# TDII_CPU_R00.net
KiCad netlist of a schematic drawn in Altium Designer
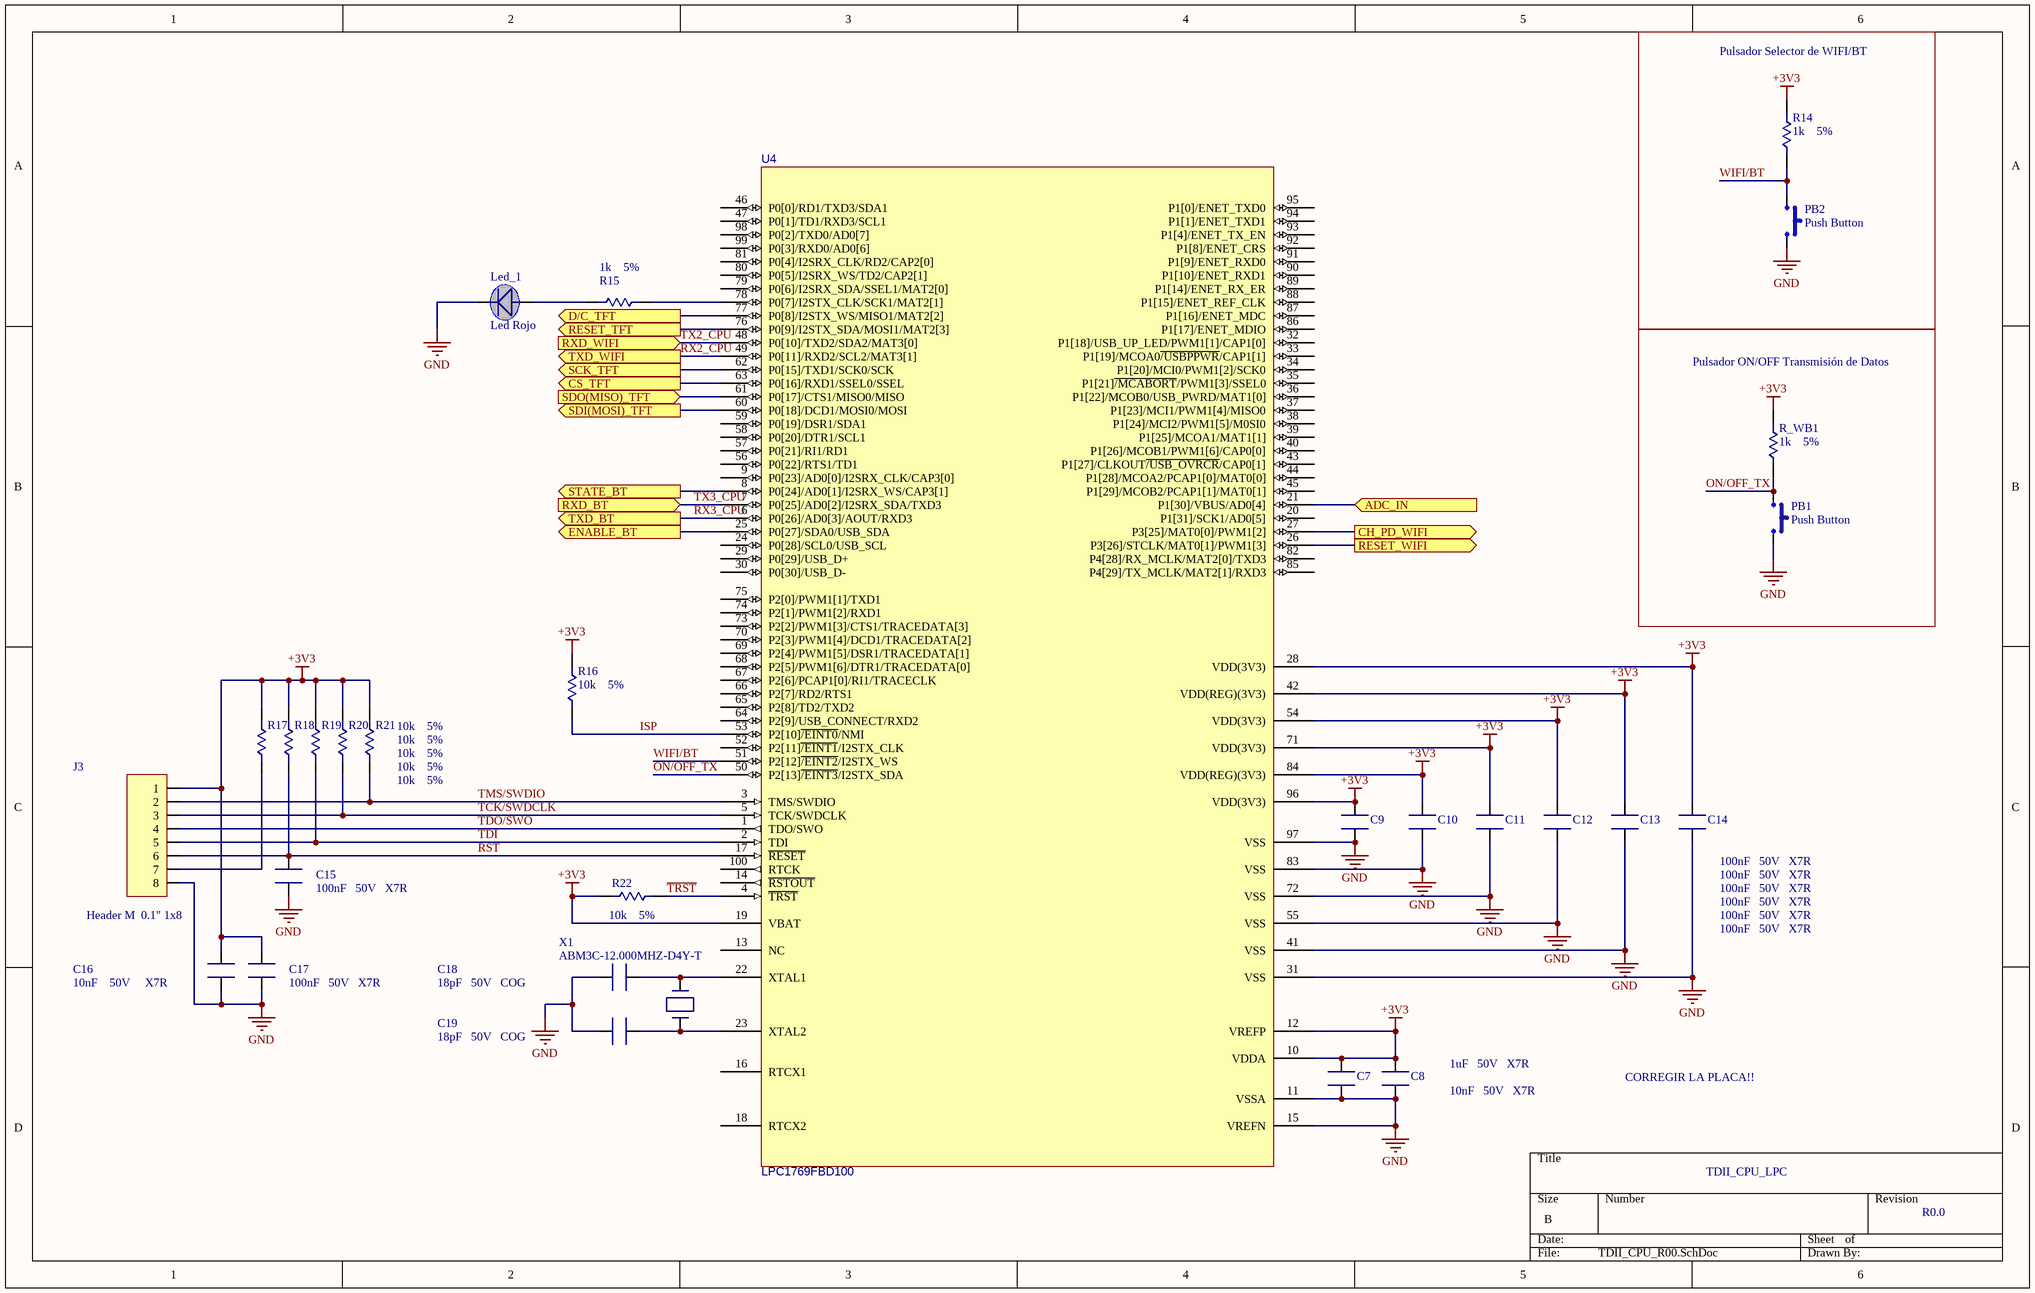
[diagram p0: TDII_CPU_R00.SchDoc]

(export (version "E")
  (design (tool "Eeschema 10.0.6"))
  (components
    (comp (ref "C7")
      (value "10nF   50V   X7R")
      (footprint "C_0805")
      (libsource (lib "TDII_SCH_LIB_R00") (part "CAP"))
    )
    (comp (ref "C8")
      (value "1uF   50V   X7R")
      (footprint "C_0805")
      (libsource (lib "TDII_SCH_LIB_R00") (part "CAP"))
    )
    (comp (ref "C9")
      (value "100nF   50V   X7R")
      (footprint "C_0805")
      (libsource (lib "TDII_SCH_LIB_R00") (part "CAP"))
    )
    (comp (ref "C10")
      (value "100nF   50V   X7R")
      (footprint "C_0805")
      (libsource (lib "TDII_SCH_LIB_R00") (part "CAP"))
    )
    (comp (ref "C11")
      (value "100nF   50V   X7R")
      (footprint "C_0805")
      (libsource (lib "TDII_SCH_LIB_R00") (part "CAP"))
    )
    (comp (ref "C12")
      (value "100nF   50V   X7R")
      (footprint "C_0805")
      (libsource (lib "TDII_SCH_LIB_R00") (part "CAP"))
    )
    (comp (ref "C13")
      (value "100nF   50V   X7R")
      (footprint "C_0805")
      (libsource (lib "TDII_SCH_LIB_R00") (part "CAP"))
    )
    (comp (ref "C14")
      (value "100nF   50V   X7R")
      (footprint "C_0805")
      (libsource (lib "TDII_SCH_LIB_R00") (part "CAP"))
    )
    (comp (ref "C15") (value "100nF   50V   X7R") (footprint "C_0805") (libsource (lib "") (part "CAP_1")))
    (comp (ref "C16") (value "10nF    50V     X7R") (footprint "C_0805") (libsource (lib "") (part "CAP_1")))
    (comp (ref "C17") (value "100nF   50V   X7R") (footprint "C_0805") (libsource (lib "") (part "CAP_1")))
    (comp (ref "C18")
      (value "18pF   50V   COG")
      (footprint "C_0805")
      (libsource (lib "TDII_SCH_LIB_R00") (part "CAP"))
    )
    (comp (ref "C19")
      (value "18pF   50V   COG")
      (footprint "C_0805")
      (libsource (lib "TDII_SCH_LIB_R00") (part "CAP"))
    )
    (comp (ref "J3")
      (value "Header M  0.1\" 1x8")
      (footprint "Header_THT")
      (libsource (lib "TDII_SCH_LIB_R00") (part "Header"))
    )
    (comp (ref "Led_1")
      (value "Led Rojo")
      (footprint "LED_0805")
      (libsource (lib "TDII_SCH_LIB_R00") (part "LED"))
    )
    (comp (ref "PB1")
      (value "Push Button")
      (footprint "HEADER_1x2")
      (libsource (lib "IFS_Altium") (part "Push Button"))
    )
    (comp (ref "PB2")
      (value "Push Button")
      (footprint "HEADER_1x2")
      (libsource (lib "IFS_Altium") (part "Push Button"))
    )
    (comp (ref "R14")
      (value "1k    5%")
      (footprint "R_0805")
      (libsource (lib "TDII_SCH_LIB_R00") (part "RES"))
    )
    (comp (ref "R15")
      (value "1k    5%")
      (footprint "R_0805")
      (libsource (lib "TDII_SCH_LIB_R00") (part "RES"))
    )
    (comp (ref "R16")
      (value "10k    5%")
      (footprint "R_0805")
      (libsource (lib "TDII_SCH_LIB_R00") (part "RES"))
    )
    (comp (ref "R17")
      (value "10k    5%")
      (footprint "R_0805")
      (libsource (lib "TDII_SCH_LIB_R00") (part "RES"))
    )
    (comp (ref "R18")
      (value "10k    5%")
      (footprint "R_0805")
      (libsource (lib "TDII_SCH_LIB_R00") (part "RES"))
    )
    (comp (ref "R19")
      (value "10k    5%")
      (footprint "R_0805")
      (libsource (lib "TDII_SCH_LIB_R00") (part "RES"))
    )
    (comp (ref "R20")
      (value "10k    5%")
      (footprint "R_0805")
      (libsource (lib "TDII_SCH_LIB_R00") (part "RES"))
    )
    (comp (ref "R21")
      (value "10k    5%")
      (footprint "R_0805")
      (libsource (lib "TDII_SCH_LIB_R00") (part "RES"))
    )
    (comp (ref "R22")
      (value "10k    5%")
      (footprint "R_0805")
      (libsource (lib "TDII_SCH_LIB_R00") (part "RES"))
    )
    (comp (ref "R_WB1")
      (value "1k    5%")
      (footprint "R_0805")
      (libsource (lib "TDII_SCH_LIB_R00") (part "RES"))
    )
    (comp (ref "U4")
      (value "LPC1769FBD100")
      (footprint "LQFP100")
      (description "CPU Cortex M3")
      (fields (field (name "DIGI-KEY PART NUMBER") "568-4966-ND"))
      (libsource (lib "TdiiCpu") (part "LPC1768FBD100"))
    )
    (comp (ref "X1")
      (value "ABM3C-12.000MHZ-D4Y-T")
      (footprint "ABM3C")
      (fields (field (name "DIGI-KEY PART NUMBER") "535-11281-1-ND"))
      (libsource (lib "TDII_SCH_LIB_R00") (part "ABM3_CRISTAL"))
    )
  )
  (nets
    (net (code "1") (name "+3V3") (class "Default")
      (node (ref "C10") (pin "1") (pinfunction "1_1") (pintype "passive"))
      (node (ref "C11") (pin "1") (pinfunction "1_1") (pintype "passive"))
      (node (ref "C12") (pin "1") (pinfunction "1_1") (pintype "passive"))
      (node (ref "C13") (pin "1") (pinfunction "1_1") (pintype "passive"))
      (node (ref "C14") (pin "1") (pinfunction "1_1") (pintype "passive"))
      (node (ref "C16") (pin "1") (pinfunction "1_1") (pintype "passive"))
      (node (ref "C17") (pin "1") (pinfunction "1_1") (pintype "passive"))
      (node (ref "C7") (pin "1") (pinfunction "1_1") (pintype "passive"))
      (node (ref "C8") (pin "1") (pinfunction "1_1") (pintype "passive"))
      (node (ref "C9") (pin "1") (pinfunction "1_1") (pintype "passive"))
      (node (ref "J3") (pin "1") (pinfunction "1_1") (pintype "passive"))
      (node (ref "R14") (pin "2") (pinfunction "2_2") (pintype "passive"))
      (node (ref "R16") (pin "2") (pinfunction "2_2") (pintype "passive"))
      (node (ref "R17") (pin "2") (pinfunction "2_2") (pintype "passive"))
      (node (ref "R18") (pin "2") (pinfunction "2_2") (pintype "passive"))
      (node (ref "R19") (pin "2") (pinfunction "2_2") (pintype "passive"))
      (node (ref "R20") (pin "2") (pinfunction "2_2") (pintype "passive"))
      (node (ref "R21") (pin "2") (pinfunction "2_2") (pintype "passive"))
      (node (ref "R22") (pin "1") (pinfunction "1_1") (pintype "passive"))
      (node (ref "R_WB1") (pin "2") (pinfunction "2_2") (pintype "passive"))
      (node (ref "U4") (pin "10") (pinfunction "VDDA_10") (pintype "power_in"))
      (node (ref "U4") (pin "12") (pinfunction "VREFP_12") (pintype "power_in"))
      (node (ref "U4") (pin "19") (pinfunction "VBAT_19") (pintype "power_in"))
      (node (ref "U4") (pin "28") (pinfunction "VDD(3V3)_28") (pintype "power_in"))
      (node (ref "U4") (pin "42") (pinfunction "VDD(REG)(3V3)_42") (pintype "power_in"))
      (node (ref "U4") (pin "54") (pinfunction "VDD(3V3)_54") (pintype "power_in"))
      (node (ref "U4") (pin "71") (pinfunction "VDD(3V3)_71") (pintype "power_in"))
      (node (ref "U4") (pin "84") (pinfunction "VDD(REG)(3V3)_84") (pintype "power_in"))
      (node (ref "U4") (pin "96") (pinfunction "VDD(3V3)_96") (pintype "power_in"))
    )
    (net (code "2") (name "/ADC_IN") (class "Default")
      (node (ref "U4") (pin "21") (pinfunction "P1[30]/VBUS/AD0[4]_21") (pintype "bidirectional"))
    )
    (net (code "3") (name "/CH_PD_WIFI") (class "Default")
      (node (ref "U4") (pin "27") (pinfunction "P3[25]/MAT0[0]/PWM1[2]_27") (pintype "bidirectional"))
    )
    (net (code "4") (name "/CS_TFT") (class "Default")
      (node (ref "U4") (pin "63") (pinfunction "P0[16]/RXD1/SSEL0/SSEL_63") (pintype "bidirectional"))
    )
    (net (code "5") (name "/D{slash}C_TFT") (class "Default")
      (node (ref "U4") (pin "77") (pinfunction "P0[8]/I2STX_WS/MISO1/MAT2[2]_77") (pintype "bidirectional"))
    )
    (net (code "6") (name "/ENABLE_BT") (class "Default")
      (node (ref "U4") (pin "25") (pinfunction "P0[27]/SDA0/USB_SDA_25") (pintype "bidirectional"))
    )
    (net (code "7") (name "/ISP") (class "Default")
      (node (ref "R16") (pin "1") (pinfunction "1_1") (pintype "passive"))
      (node (ref "U4") (pin "53") (pinfunction "P2[10]~{/EINT0}/NMI_53") (pintype "bidirectional"))
    )
    (net (code "8") (name "/ON{slash}OFF_TX") (class "Default")
      (node (ref "PB1") (pin "1") (pinfunction "1_1") (pintype "passive"))
      (node (ref "R_WB1") (pin "1") (pinfunction "1_1") (pintype "passive"))
      (node (ref "U4") (pin "50") (pinfunction "P2[13]~{/EINT3}/I2STX_SDA_50") (pintype "bidirectional"))
    )
    (net (code "9") (name "/RESET_TFT") (class "Default")
      (node (ref "U4") (pin "76") (pinfunction "P0[9]/I2STX_SDA/MOSI1/MAT2[3]_76") (pintype "bidirectional"))
    )
    (net (code "10") (name "/RESET_WIFI") (class "Default")
      (node (ref "U4") (pin "26") (pinfunction "P3[26]/STCLK/MAT0[1]/PWM1[3]_26") (pintype "bidirectional"))
    )
    (net (code "11") (name "/RST") (class "Default")
      (node (ref "C15") (pin "1") (pinfunction "1_1") (pintype "passive"))
      (node (ref "J3") (pin "6") (pinfunction "6_6") (pintype "passive"))
      (node (ref "R18") (pin "1") (pinfunction "1_1") (pintype "passive"))
      (node (ref "U4") (pin "17") (pinfunction "~{RESET}_17") (pintype "input"))
    )
    (net (code "12") (name "/RX2_CPU") (class "Default")
      (node (ref "U4") (pin "49") (pinfunction "P0[11]/RXD2/SCL2/MAT3[1]_49") (pintype "bidirectional"))
    )
    (net (code "13") (name "/RX3_CPU") (class "Default")
      (node (ref "U4") (pin "6") (pinfunction "P0[26]/AD0[3]/AOUT/RXD3_6") (pintype "bidirectional"))
    )
    (net (code "14") (name "/SCK_TFT") (class "Default")
      (node (ref "U4") (pin "62") (pinfunction "P0[15]/TXD1/SCK0/SCK_62") (pintype "bidirectional"))
    )
    (net (code "15") (name "/SDI(MOSI)_TFT") (class "Default")
      (node (ref "U4") (pin "60") (pinfunction "P0[18]/DCD1/MOSI0/MOSI_60") (pintype "bidirectional"))
    )
    (net (code "16") (name "/SDO(MISO)_TFT") (class "Default")
      (node (ref "U4") (pin "61") (pinfunction "P0[17]/CTS1/MISO0/MISO_61") (pintype "bidirectional"))
    )
    (net (code "17") (name "/STATE_BT") (class "Default")
      (node (ref "U4") (pin "8") (pinfunction "P0[24]/AD0[1]/I2SRX_WS/CAP3[1]_8") (pintype "bidirectional"))
    )
    (net (code "18") (name "/TCK{slash}SWDCLK") (class "Default")
      (node (ref "J3") (pin "3") (pinfunction "3_3") (pintype "passive"))
      (node (ref "R20") (pin "1") (pinfunction "1_1") (pintype "passive"))
      (node (ref "U4") (pin "5") (pinfunction "TCK/SWDCLK_5") (pintype "input"))
    )
    (net (code "19") (name "/TDI") (class "Default")
      (node (ref "J3") (pin "5") (pinfunction "5_5") (pintype "passive"))
      (node (ref "R19") (pin "1") (pinfunction "1_1") (pintype "passive"))
      (node (ref "U4") (pin "2") (pinfunction "TDI_2") (pintype "input"))
    )
    (net (code "20") (name "/TDO{slash}SWO") (class "Default")
      (node (ref "J3") (pin "4") (pinfunction "4_4") (pintype "passive"))
      (node (ref "U4") (pin "1") (pinfunction "TDO/SWO_1") (pintype "output"))
    )
    (net (code "21") (name "/TMS{slash}SWDIO") (class "Default")
      (node (ref "J3") (pin "2") (pinfunction "2_2") (pintype "passive"))
      (node (ref "R21") (pin "1") (pinfunction "1_1") (pintype "passive"))
      (node (ref "U4") (pin "3") (pinfunction "TMS/SWDIO_3") (pintype "input"))
    )
    (net (code "22") (name "/TX2_CPU") (class "Default")
      (node (ref "U4") (pin "48") (pinfunction "P0[10]/TXD2/SDA2/MAT3[0]_48") (pintype "bidirectional"))
    )
    (net (code "23") (name "/TX3_CPU") (class "Default")
      (node (ref "U4") (pin "7") (pinfunction "P0[25]/AD0[2]/I2SRX_SDA/TXD3_7") (pintype "bidirectional"))
    )
    (net (code "24") (name "/WIFI{slash}BT") (class "Default")
      (node (ref "PB2") (pin "1") (pinfunction "1_1") (pintype "passive"))
      (node (ref "R14") (pin "1") (pinfunction "1_1") (pintype "passive"))
      (node (ref "U4") (pin "51") (pinfunction "P2[12]~{/EINT2}/I2STX_WS_51") (pintype "bidirectional"))
    )
    (net (code "25") (name "/~{TRST}") (class "Default")
      (node (ref "R22") (pin "2") (pinfunction "2_2") (pintype "passive"))
      (node (ref "U4") (pin "4") (pinfunction "~{TRST}_4") (pintype "input"))
    )
    (net (code "26") (name "GND") (class "Default")
      (node (ref "C10") (pin "2") (pinfunction "2_2") (pintype "passive"))
      (node (ref "C11") (pin "2") (pinfunction "2_2") (pintype "passive"))
      (node (ref "C12") (pin "2") (pinfunction "2_2") (pintype "passive"))
      (node (ref "C13") (pin "2") (pinfunction "2_2") (pintype "passive"))
      (node (ref "C14") (pin "2") (pinfunction "2_2") (pintype "passive"))
      (node (ref "C15") (pin "2") (pinfunction "2_2") (pintype "passive"))
      (node (ref "C16") (pin "2") (pinfunction "2_2") (pintype "passive"))
      (node (ref "C17") (pin "2") (pinfunction "2_2") (pintype "passive"))
      (node (ref "C18") (pin "1") (pinfunction "1_1") (pintype "passive"))
      (node (ref "C19") (pin "1") (pinfunction "1_1") (pintype "passive"))
      (node (ref "C7") (pin "2") (pinfunction "2_2") (pintype "passive"))
      (node (ref "C8") (pin "2") (pinfunction "2_2") (pintype "passive"))
      (node (ref "C9") (pin "2") (pinfunction "2_2") (pintype "passive"))
      (node (ref "J3") (pin "8") (pinfunction "8_8") (pintype "passive"))
      (node (ref "Led_1") (pin "2") (pinfunction "2_2") (pintype "passive"))
      (node (ref "PB1") (pin "2") (pinfunction "2_2") (pintype "passive"))
      (node (ref "PB2") (pin "2") (pinfunction "2_2") (pintype "passive"))
      (node (ref "U4") (pin "11") (pinfunction "VSSA_11") (pintype "power_in"))
      (node (ref "U4") (pin "15") (pinfunction "VREFN_15") (pintype "power_in"))
      (node (ref "U4") (pin "31") (pinfunction "VSS_31") (pintype "power_in"))
      (node (ref "U4") (pin "41") (pinfunction "VSS_41") (pintype "power_in"))
      (node (ref "U4") (pin "55") (pinfunction "VSS_55") (pintype "power_in"))
      (node (ref "U4") (pin "72") (pinfunction "VSS_72") (pintype "power_in"))
      (node (ref "U4") (pin "83") (pinfunction "VSS_83") (pintype "power_in"))
      (node (ref "U4") (pin "97") (pinfunction "VSS_97") (pintype "power_in"))
    )
    (net (code "27") (name "Net-(J3-Pad7)") (class "Default")
      (node (ref "J3") (pin "7") (pinfunction "7_7") (pintype "passive"))
      (node (ref "R17") (pin "1") (pinfunction "1_1") (pintype "passive"))
    )
    (net (code "28") (name "Net-(Led_1-Pad1)") (class "Default")
      (node (ref "Led_1") (pin "1") (pinfunction "1_1") (pintype "passive"))
      (node (ref "R15") (pin "1") (pinfunction "1_1") (pintype "passive"))
    )
    (net (code "29") (name "Net-(U4-P0[7]{slash}I2STX_CLK{slash}SCK1{slash}MAT2[1])") (class "Default")
      (node (ref "R15") (pin "2") (pinfunction "2_2") (pintype "passive"))
      (node (ref "U4") (pin "78") (pinfunction "P0[7]/I2STX_CLK/SCK1/MAT2[1]_78") (pintype "bidirectional"))
    )
    (net (code "30") (name "Net-(U4-XTAL1)") (class "Default")
      (node (ref "C18") (pin "2") (pinfunction "2_2") (pintype "passive"))
      (node (ref "U4") (pin "22") (pinfunction "XTAL1_22") (pintype "passive"))
      (node (ref "X1") (pin "1") (pinfunction "1_1") (pintype "passive"))
    )
    (net (code "31") (name "Net-(U4-XTAL2)") (class "Default")
      (node (ref "C19") (pin "2") (pinfunction "2_2") (pintype "passive"))
      (node (ref "U4") (pin "23") (pinfunction "XTAL2_23") (pintype "passive"))
      (node (ref "X1") (pin "3") (pinfunction "3_3") (pintype "passive"))
    )
    (net (code "32") (name "unconnected-(U4-NC-Pad13)") (class "Default")
      (node (ref "U4") (pin "13") (pinfunction "NC_13") (pintype "passive"))
    )
    (net (code "33") (name "unconnected-(U4-P0[0]{slash}RD1{slash}TXD3{slash}SDA1-Pad46)") (class "Default")
      (node (ref "U4") (pin "46") (pinfunction "P0[0]/RD1/TXD3/SDA1_46") (pintype "bidirectional"))
    )
    (net (code "34") (name "unconnected-(U4-P0[1]{slash}TD1{slash}RXD3{slash}SCL1-Pad47)") (class "Default")
      (node (ref "U4") (pin "47") (pinfunction "P0[1]/TD1/RXD3/SCL1_47") (pintype "bidirectional"))
    )
    (net (code "35") (name "unconnected-(U4-P0[2]{slash}TXD0{slash}AD0[7]-Pad98)") (class "Default")
      (node (ref "U4") (pin "98") (pinfunction "P0[2]/TXD0/AD0[7]_98") (pintype "bidirectional"))
    )
    (net (code "36") (name "unconnected-(U4-P0[3]{slash}RXD0{slash}AD0[6]-Pad99)") (class "Default")
      (node (ref "U4") (pin "99") (pinfunction "P0[3]/RXD0/AD0[6]_99") (pintype "bidirectional"))
    )
    (net (code "37") (name "unconnected-(U4-P0[4]{slash}I2SRX_CLK{slash}RD2{slash}CAP2[0]-Pad81)") (class "Default")
      (node (ref "U4") (pin "81") (pinfunction "P0[4]/I2SRX_CLK/RD2/CAP2[0]_81") (pintype "bidirectional"))
    )
    (net (code "38") (name "unconnected-(U4-P0[5]{slash}I2SRX_WS{slash}TD2{slash}CAP2[1]-Pad80)") (class "Default")
      (node (ref "U4") (pin "80") (pinfunction "P0[5]/I2SRX_WS/TD2/CAP2[1]_80") (pintype "bidirectional"))
    )
    (net (code "39") (name "unconnected-(U4-P0[6]{slash}I2SRX_SDA{slash}SSEL1{slash}MAT2[0]-Pad79)") (class "Default")
      (node (ref "U4") (pin "79") (pinfunction "P0[6]/I2SRX_SDA/SSEL1/MAT2[0]_79") (pintype "bidirectional"))
    )
    (net (code "40") (name "unconnected-(U4-P0[19]{slash}DSR1{slash}SDA1-Pad59)") (class "Default")
      (node (ref "U4") (pin "59") (pinfunction "P0[19]/DSR1/SDA1_59") (pintype "bidirectional"))
    )
    (net (code "41") (name "unconnected-(U4-P0[20]{slash}DTR1{slash}SCL1-Pad58)") (class "Default")
      (node (ref "U4") (pin "58") (pinfunction "P0[20]/DTR1/SCL1_58") (pintype "bidirectional"))
    )
    (net (code "42") (name "unconnected-(U4-P0[21]{slash}RI1{slash}RD1-Pad57)") (class "Default")
      (node (ref "U4") (pin "57") (pinfunction "P0[21]/RI1/RD1_57") (pintype "bidirectional"))
    )
    (net (code "43") (name "unconnected-(U4-P0[22]{slash}RTS1{slash}TD1-Pad56)") (class "Default")
      (node (ref "U4") (pin "56") (pinfunction "P0[22]/RTS1/TD1_56") (pintype "bidirectional"))
    )
    (net (code "44") (name "unconnected-(U4-P0[23]{slash}AD0[0]{slash}I2SRX_CLK{slash}CAP3[0]-Pad9)") (class "Default")
      (node (ref "U4") (pin "9") (pinfunction "P0[23]/AD0[0]/I2SRX_CLK/CAP3[0]_9") (pintype "bidirectional"))
    )
    (net (code "45") (name "unconnected-(U4-P0[28]{slash}SCL0{slash}USB_SCL-Pad24)") (class "Default")
      (node (ref "U4") (pin "24") (pinfunction "P0[28]/SCL0/USB_SCL_24") (pintype "bidirectional"))
    )
    (net (code "46") (name "unconnected-(U4-P0[29]{slash}USB_D+-Pad29)") (class "Default")
      (node (ref "U4") (pin "29") (pinfunction "P0[29]/USB_D+_29") (pintype "bidirectional"))
    )
    (net (code "47") (name "unconnected-(U4-P0[30]{slash}USB_D--Pad30)") (class "Default")
      (node (ref "U4") (pin "30") (pinfunction "P0[30]/USB_D-_30") (pintype "bidirectional"))
    )
    (net (code "48") (name "unconnected-(U4-P1[0]{slash}ENET_TXD0-Pad95)") (class "Default")
      (node (ref "U4") (pin "95") (pinfunction "P1[0]/ENET_TXD0_95") (pintype "bidirectional"))
    )
    (net (code "49") (name "unconnected-(U4-P1[1]{slash}ENET_TXD1-Pad94)") (class "Default")
      (node (ref "U4") (pin "94") (pinfunction "P1[1]/ENET_TXD1_94") (pintype "bidirectional"))
    )
    (net (code "50") (name "unconnected-(U4-P1[4]{slash}ENET_TX_EN-Pad93)") (class "Default")
      (node (ref "U4") (pin "93") (pinfunction "P1[4]/ENET_TX_EN_93") (pintype "bidirectional"))
    )
    (net (code "51") (name "unconnected-(U4-P1[8]{slash}ENET_CRS-Pad92)") (class "Default")
      (node (ref "U4") (pin "92") (pinfunction "P1[8]/ENET_CRS_92") (pintype "bidirectional"))
    )
    (net (code "52") (name "unconnected-(U4-P1[9]{slash}ENET_RXD0-Pad91)") (class "Default")
      (node (ref "U4") (pin "91") (pinfunction "P1[9]/ENET_RXD0_91") (pintype "bidirectional"))
    )
    (net (code "53") (name "unconnected-(U4-P1[10]{slash}ENET_RXD1-Pad90)") (class "Default")
      (node (ref "U4") (pin "90") (pinfunction "P1[10]/ENET_RXD1_90") (pintype "bidirectional"))
    )
    (net (code "54") (name "unconnected-(U4-P1[14]{slash}ENET_RX_ER-Pad89)") (class "Default")
      (node (ref "U4") (pin "89") (pinfunction "P1[14]/ENET_RX_ER_89") (pintype "bidirectional"))
    )
    (net (code "55") (name "unconnected-(U4-P1[15]{slash}ENET_REF_CLK-Pad88)") (class "Default")
      (node (ref "U4") (pin "88") (pinfunction "P1[15]/ENET_REF_CLK_88") (pintype "bidirectional"))
    )
    (net (code "56") (name "unconnected-(U4-P1[16]{slash}ENET_MDC-Pad87)") (class "Default")
      (node (ref "U4") (pin "87") (pinfunction "P1[16]/ENET_MDC_87") (pintype "bidirectional"))
    )
    (net (code "57") (name "unconnected-(U4-P1[17]{slash}ENET_MDIO-Pad86)") (class "Default")
      (node (ref "U4") (pin "86") (pinfunction "P1[17]/ENET_MDIO_86") (pintype "bidirectional"))
    )
    (net (code "58") (name "unconnected-(U4-P1[18]{slash}USB_UP_LED{slash}PWM1[1]{slash}CAP1[0]-Pad32)") (class "Default")
      (node (ref "U4") (pin "32") (pinfunction "P1[18]/USB_UP_LED/PWM1[1]/CAP1[0]_32") (pintype "bidirectional"))
    )
    (net (code "59") (name "unconnected-(U4-P1[19]{slash}MCOA0~{{slash}USBPPWR}{slash}CAP1[1]-Pad33)") (class "Default")
      (node (ref "U4") (pin "33") (pinfunction "P1[19]/MCOA0~{/USBPPWR}/CAP1[1]_33") (pintype "bidirectional"))
    )
    (net (code "60") (name "unconnected-(U4-P1[20]{slash}MCI0{slash}PWM1[2]{slash}SCK0-Pad34)") (class "Default")
      (node (ref "U4") (pin "34") (pinfunction "P1[20]/MCI0/PWM1[2]/SCK0_34") (pintype "bidirectional"))
    )
    (net (code "61") (name "unconnected-(U4-P1[21]~{{slash}MCABORT}{slash}PWM1[3]{slash}SSEL0-Pad35)") (class "Default")
      (node (ref "U4") (pin "35") (pinfunction "P1[21]~{/MCABORT}/PWM1[3]/SSEL0_35") (pintype "bidirectional"))
    )
    (net (code "62") (name "unconnected-(U4-P1[22]{slash}MCOB0{slash}USB_PWRD{slash}MAT1[0]-Pad36)") (class "Default")
      (node (ref "U4") (pin "36") (pinfunction "P1[22]/MCOB0/USB_PWRD/MAT1[0]_36") (pintype "bidirectional"))
    )
    (net (code "63") (name "unconnected-(U4-P1[23]{slash}MCI1{slash}PWM1[4]{slash}MISO0-Pad37)") (class "Default")
      (node (ref "U4") (pin "37") (pinfunction "P1[23]/MCI1/PWM1[4]/MISO0_37") (pintype "bidirectional"))
    )
    (net (code "64") (name "unconnected-(U4-P1[24]{slash}MCI2{slash}PWM1[5]{slash}M0SI0-Pad38)") (class "Default")
      (node (ref "U4") (pin "38") (pinfunction "P1[24]/MCI2/PWM1[5]/M0SI0_38") (pintype "bidirectional"))
    )
    (net (code "65") (name "unconnected-(U4-P1[25]{slash}MCOA1{slash}MAT1[1]-Pad39)") (class "Default")
      (node (ref "U4") (pin "39") (pinfunction "P1[25]/MCOA1/MAT1[1]_39") (pintype "bidirectional"))
    )
    (net (code "66") (name "unconnected-(U4-P1[26]{slash}MCOB1{slash}PWM1[6]{slash}CAP0[0]-Pad40)") (class "Default")
      (node (ref "U4") (pin "40") (pinfunction "P1[26]/MCOB1/PWM1[6]/CAP0[0]_40") (pintype "bidirectional"))
    )
    (net (code "67") (name "unconnected-(U4-P1[27]{slash}CLKOUT~{{slash}USB_OVRCR}{slash}CAP0[1]-Pad43)") (class "Default")
      (node (ref "U4") (pin "43") (pinfunction "P1[27]/CLKOUT~{/USB_OVRCR}/CAP0[1]_43") (pintype "bidirectional"))
    )
    (net (code "68") (name "unconnected-(U4-P1[28]{slash}MCOA2{slash}PCAP1[0]{slash}MAT0[0]-Pad44)") (class "Default")
      (node (ref "U4") (pin "44") (pinfunction "P1[28]/MCOA2/PCAP1[0]/MAT0[0]_44") (pintype "bidirectional"))
    )
    (net (code "69") (name "unconnected-(U4-P1[29]{slash}MCOB2{slash}PCAP1[1]{slash}MAT0[1]-Pad45)") (class "Default")
      (node (ref "U4") (pin "45") (pinfunction "P1[29]/MCOB2/PCAP1[1]/MAT0[1]_45") (pintype "bidirectional"))
    )
    (net (code "70") (name "unconnected-(U4-P1[31]{slash}SCK1{slash}AD0[5]-Pad20)") (class "Default")
      (node (ref "U4") (pin "20") (pinfunction "P1[31]/SCK1/AD0[5]_20") (pintype "bidirectional"))
    )
    (net (code "71") (name "unconnected-(U4-P2[0]{slash}PWM1[1]{slash}TXD1-Pad75)") (class "Default")
      (node (ref "U4") (pin "75") (pinfunction "P2[0]/PWM1[1]/TXD1_75") (pintype "bidirectional"))
    )
    (net (code "72") (name "unconnected-(U4-P2[1]{slash}PWM1[2]{slash}RXD1-Pad74)") (class "Default")
      (node (ref "U4") (pin "74") (pinfunction "P2[1]/PWM1[2]/RXD1_74") (pintype "bidirectional"))
    )
    (net (code "73") (name "unconnected-(U4-P2[2]{slash}PWM1[3]{slash}CTS1{slash}TRACEDATA[3]-Pad73)") (class "Default")
      (node (ref "U4") (pin "73") (pinfunction "P2[2]/PWM1[3]/CTS1/TRACEDATA[3]_73") (pintype "bidirectional"))
    )
    (net (code "74") (name "unconnected-(U4-P2[3]{slash}PWM1[4]{slash}DCD1{slash}TRACEDATA[2]-Pad70)") (class "Default")
      (node (ref "U4") (pin "70") (pinfunction "P2[3]/PWM1[4]/DCD1/TRACEDATA[2]_70") (pintype "bidirectional"))
    )
    (net (code "75") (name "unconnected-(U4-P2[4]{slash}PWM1[5]{slash}DSR1{slash}TRACEDATA[1]-Pad69)") (class "Default")
      (node (ref "U4") (pin "69") (pinfunction "P2[4]/PWM1[5]/DSR1/TRACEDATA[1]_69") (pintype "bidirectional"))
    )
    (net (code "76") (name "unconnected-(U4-P2[5]{slash}PWM1[6]{slash}DTR1{slash}TRACEDATA[0]-Pad68)") (class "Default")
      (node (ref "U4") (pin "68") (pinfunction "P2[5]/PWM1[6]/DTR1/TRACEDATA[0]_68") (pintype "bidirectional"))
    )
    (net (code "77") (name "unconnected-(U4-P2[6]{slash}PCAP1[0]{slash}RI1{slash}TRACECLK-Pad67)") (class "Default")
      (node (ref "U4") (pin "67") (pinfunction "P2[6]/PCAP1[0]/RI1/TRACECLK_67") (pintype "bidirectional"))
    )
    (net (code "78") (name "unconnected-(U4-P2[7]{slash}RD2{slash}RTS1-Pad66)") (class "Default")
      (node (ref "U4") (pin "66") (pinfunction "P2[7]/RD2/RTS1_66") (pintype "bidirectional"))
    )
    (net (code "79") (name "unconnected-(U4-P2[8]{slash}TD2{slash}TXD2-Pad65)") (class "Default")
      (node (ref "U4") (pin "65") (pinfunction "P2[8]/TD2/TXD2_65") (pintype "bidirectional"))
    )
    (net (code "80") (name "unconnected-(U4-P2[9]{slash}USB_CONNECT{slash}RXD2-Pad64)") (class "Default")
      (node (ref "U4") (pin "64") (pinfunction "P2[9]/USB_CONNECT/RXD2_64") (pintype "bidirectional"))
    )
    (net (code "81") (name "unconnected-(U4-P2[11]~{{slash}EINT1}{slash}I2STX_CLK-Pad52)") (class "Default")
      (node (ref "U4") (pin "52") (pinfunction "P2[11]~{/EINT1}/I2STX_CLK_52") (pintype "bidirectional"))
    )
    (net (code "82") (name "unconnected-(U4-P4[28]{slash}RX_MCLK{slash}MAT2[0]{slash}TXD3-Pad82)") (class "Default")
      (node (ref "U4") (pin "82") (pinfunction "P4[28]/RX_MCLK/MAT2[0]/TXD3_82") (pintype "bidirectional"))
    )
    (net (code "83") (name "unconnected-(U4-P4[29]{slash}TX_MCLK{slash}MAT2[1]{slash}RXD3-Pad85)") (class "Default")
      (node (ref "U4") (pin "85") (pinfunction "P4[29]/TX_MCLK/MAT2[1]/RXD3_85") (pintype "bidirectional"))
    )
    (net (code "84") (name "unconnected-(U4-RTCK-Pad100)") (class "Default")
      (node (ref "U4") (pin "100") (pinfunction "RTCK_100") (pintype "output"))
    )
    (net (code "85") (name "unconnected-(U4-RTCX1-Pad16)") (class "Default")
      (node (ref "U4") (pin "16") (pinfunction "RTCX1_16") (pintype "passive"))
    )
    (net (code "86") (name "unconnected-(U4-RTCX2-Pad18)") (class "Default")
      (node (ref "U4") (pin "18") (pinfunction "RTCX2_18") (pintype "passive"))
    )
    (net (code "87") (name "unconnected-(U4-~{RSTOUT}-Pad14)") (class "Default")
      (node (ref "U4") (pin "14") (pinfunction "~{RSTOUT}_14") (pintype "output"))
    )
  )
)
